# main.net
KiCad netlist of a schematic drawn in EAGLE
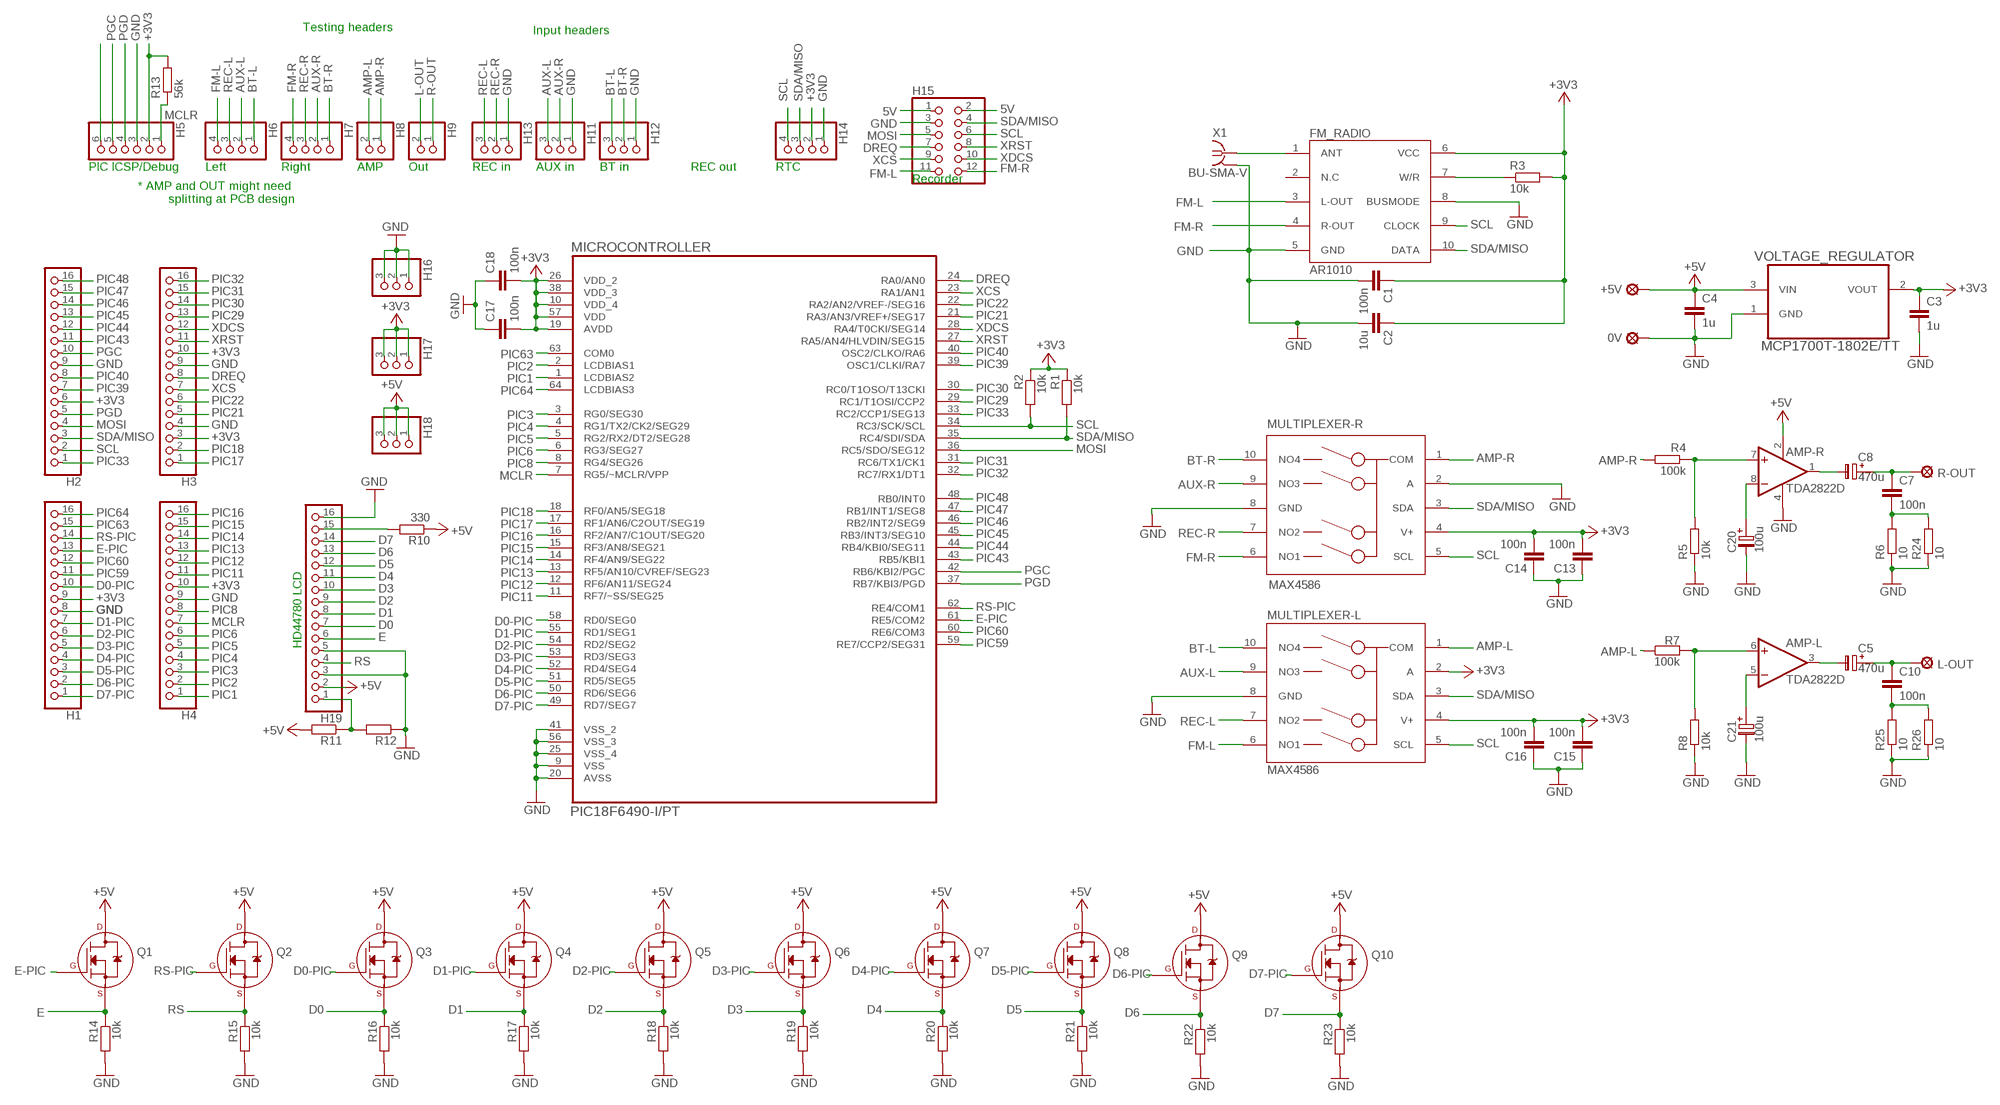
[diagram p0: schematic, sheet 1]

(export (version "E")
  (design (tool "Eeschema 10.0.6"))
  (components
    (comp (ref "+5V")
      (value "LSP11")
      (footprint "eagle-import:LSP11")
      (libsource (lib "eagle-import") (part "LSP11"))
    )
    (comp (ref "0V")
      (value "LSP11")
      (footprint "eagle-import:LSP11")
      (libsource (lib "eagle-import") (part "LSP11"))
    )
    (comp (ref "AMP-")
      (value "TDA2822D")
      (footprint "eagle-import:SO08")
      (libsource (lib "eagle-import") (part "TDA2822D"))
    )
    (comp (ref "C1")
      (value "100n")
      (footprint "eagle-import:C0805")
      (libsource (lib "eagle-import") (part "C-EUC0805"))
    )
    (comp (ref "C2")
      (value "10u")
      (footprint "eagle-import:C0805")
      (libsource (lib "eagle-import") (part "C-EUC0805"))
    )
    (comp (ref "C3")
      (value "1u")
      (footprint "eagle-import:C0805")
      (libsource (lib "eagle-import") (part "C-EUC0805"))
    )
    (comp (ref "C4")
      (value "1u")
      (footprint "eagle-import:C0805")
      (libsource (lib "eagle-import") (part "C-EUC0805"))
    )
    (comp (ref "C5")
      (value "470u")
      (footprint "eagle-import:SV-G")
      (libsource (lib "eagle-import") (part "C-PR-SMD-SV-G"))
    )
    (comp (ref "C7")
      (value "100n")
      (footprint "eagle-import:C0805")
      (libsource (lib "eagle-import") (part "C-EUC0805"))
    )
    (comp (ref "C8")
      (value "470u")
      (footprint "eagle-import:SV-G")
      (libsource (lib "eagle-import") (part "C-PR-SMD-SV-G"))
    )
    (comp (ref "C10")
      (value "100n")
      (footprint "eagle-import:C0805")
      (libsource (lib "eagle-import") (part "C-EUC0805"))
    )
    (comp (ref "C13")
      (value "100n")
      (footprint "eagle-import:C0805")
      (libsource (lib "eagle-import") (part "C-EUC0805"))
    )
    (comp (ref "C14")
      (value "100n")
      (footprint "eagle-import:C0805")
      (libsource (lib "eagle-import") (part "C-EUC0805"))
    )
    (comp (ref "C15")
      (value "100n")
      (footprint "eagle-import:C0805")
      (libsource (lib "eagle-import") (part "C-EUC0805"))
    )
    (comp (ref "C16")
      (value "100n")
      (footprint "eagle-import:C0805")
      (libsource (lib "eagle-import") (part "C-EUC0805"))
    )
    (comp (ref "C17")
      (value "100n")
      (footprint "eagle-import:C0805")
      (libsource (lib "eagle-import") (part "C-EUC0805"))
    )
    (comp (ref "C18")
      (value "100n")
      (footprint "eagle-import:C0805")
      (libsource (lib "eagle-import") (part "C-EUC0805"))
    )
    (comp (ref "C20")
      (value "100u")
      (footprint "eagle-import:SV-D")
      (libsource (lib "eagle-import") (part "C-PR-SMD-SV-D"))
    )
    (comp (ref "C21")
      (value "100u")
      (footprint "eagle-import:SV-D")
      (libsource (lib "eagle-import") (part "C-PR-SMD-SV-D"))
    )
    (comp (ref "H1")
      (value "PINHD-1X16")
      (footprint "eagle-import:1X16")
      (libsource (lib "eagle-import") (part "PINHD-1X16"))
    )
    (comp (ref "H2")
      (value "PINHD-1X16")
      (footprint "eagle-import:1X16")
      (libsource (lib "eagle-import") (part "PINHD-1X16"))
    )
    (comp (ref "H3")
      (value "PINHD-1X16")
      (footprint "eagle-import:1X16")
      (libsource (lib "eagle-import") (part "PINHD-1X16"))
    )
    (comp (ref "H4")
      (value "PINHD-1X16")
      (footprint "eagle-import:1X16")
      (libsource (lib "eagle-import") (part "PINHD-1X16"))
    )
    (comp (ref "H5")
      (value "PINHD-1X6")
      (footprint "eagle-import:1X06")
      (libsource (lib "eagle-import") (part "PINHD-1X6"))
    )
    (comp (ref "H6")
      (value "PINHD-1X4")
      (footprint "eagle-import:1X04")
      (libsource (lib "eagle-import") (part "PINHD-1X4"))
    )
    (comp (ref "H7")
      (value "PINHD-1X4")
      (footprint "eagle-import:1X04")
      (libsource (lib "eagle-import") (part "PINHD-1X4"))
    )
    (comp (ref "H8")
      (value "PINHD-1X2")
      (footprint "eagle-import:1X02")
      (libsource (lib "eagle-import") (part "PINHD-1X2"))
    )
    (comp (ref "H9")
      (value "PINHD-1X2")
      (footprint "eagle-import:1X02")
      (libsource (lib "eagle-import") (part "PINHD-1X2"))
    )
    (comp (ref "H11")
      (value "PINHD-1X3")
      (footprint "eagle-import:1X03")
      (libsource (lib "eagle-import") (part "PINHD-1X3"))
    )
    (comp (ref "H12")
      (value "PINHD-1X3")
      (footprint "eagle-import:1X03")
      (libsource (lib "eagle-import") (part "PINHD-1X3"))
    )
    (comp (ref "H13")
      (value "PINHD-1X3")
      (footprint "eagle-import:1X03")
      (libsource (lib "eagle-import") (part "PINHD-1X3"))
    )
    (comp (ref "H14")
      (value "PINHD-1X4/90")
      (footprint "eagle-import:1X04_90")
      (libsource (lib "eagle-import") (part "PINHD-1X4/90"))
    )
    (comp (ref "H15")
      (value "PINHD-2X6")
      (footprint "eagle-import:2X06")
      (libsource (lib "eagle-import") (part "PINHD-2X6"))
    )
    (comp (ref "H16")
      (value "PINHD-1X3")
      (footprint "eagle-import:1X03")
      (libsource (lib "eagle-import") (part "PINHD-1X3"))
    )
    (comp (ref "H17")
      (value "PINHD-1X3")
      (footprint "eagle-import:1X03")
      (libsource (lib "eagle-import") (part "PINHD-1X3"))
    )
    (comp (ref "H18")
      (value "PINHD-1X3")
      (footprint "eagle-import:1X03")
      (libsource (lib "eagle-import") (part "PINHD-1X3"))
    )
    (comp (ref "H19")
      (value "PINHD-1X16")
      (footprint "eagle-import:1X16")
      (libsource (lib "eagle-import") (part "PINHD-1X16"))
    )
    (comp (ref "L-OUT")
      (value "LSP10")
      (footprint "eagle-import:LSP10")
      (libsource (lib "eagle-import") (part "LSP10"))
    )
    (comp (ref "MICROCONTROLLER")
      (value "PIC18F6490-I/PT")
      (footprint "eagle-import:QFP50P1200X1200X120-64N")
      (libsource (lib "eagle-import") (part "PIC18F6490-I/PT"))
    )
    (comp (ref "Q1")
      (value "2N7000_SOT23")
      (footprint "eagle-import:SOT-23")
      (libsource (lib "eagle-import") (part "2N700_SOT230"))
    )
    (comp (ref "Q2")
      (value "2N7000_SOT23")
      (footprint "eagle-import:SOT-23")
      (libsource (lib "eagle-import") (part "2N700_SOT230"))
    )
    (comp (ref "Q3")
      (value "2N7000_SOT23")
      (footprint "eagle-import:SOT-23")
      (libsource (lib "eagle-import") (part "2N700_SOT230"))
    )
    (comp (ref "Q4")
      (value "2N7000_SOT23")
      (footprint "eagle-import:SOT-23")
      (libsource (lib "eagle-import") (part "2N700_SOT230"))
    )
    (comp (ref "Q5")
      (value "2N7000_SOT23")
      (footprint "eagle-import:SOT-23")
      (libsource (lib "eagle-import") (part "2N700_SOT230"))
    )
    (comp (ref "Q6")
      (value "2N7000_SOT23")
      (footprint "eagle-import:SOT-23")
      (libsource (lib "eagle-import") (part "2N700_SOT230"))
    )
    (comp (ref "Q7")
      (value "2N7000_SOT23")
      (footprint "eagle-import:SOT-23")
      (libsource (lib "eagle-import") (part "2N700_SOT230"))
    )
    (comp (ref "Q8")
      (value "2N7000_SOT23")
      (footprint "eagle-import:SOT-23")
      (libsource (lib "eagle-import") (part "2N700_SOT230"))
    )
    (comp (ref "Q9")
      (value "2N7000_SOT23")
      (footprint "eagle-import:SOT-23")
      (libsource (lib "eagle-import") (part "2N700_SOT230"))
    )
    (comp (ref "Q10")
      (value "2N7000_SOT23")
      (footprint "eagle-import:SOT-23")
      (libsource (lib "eagle-import") (part "2N700_SOT230"))
    )
    (comp (ref "R-OUT")
      (value "LSP10")
      (footprint "eagle-import:LSP10")
      (libsource (lib "eagle-import") (part "LSP10"))
    )
    (comp (ref "R1")
      (value "10k")
      (footprint "eagle-import:M0805")
      (libsource (lib "eagle-import") (part "R-EU_M0805"))
    )
    (comp (ref "R2")
      (value "10k")
      (footprint "eagle-import:M0805")
      (libsource (lib "eagle-import") (part "R-EU_M0805"))
    )
    (comp (ref "R3")
      (value "10k")
      (footprint "eagle-import:M0805")
      (libsource (lib "eagle-import") (part "R-EU_M0805"))
    )
    (comp (ref "R4")
      (value "100k")
      (footprint "eagle-import:M0805")
      (libsource (lib "eagle-import") (part "R-EU_M0805"))
    )
    (comp (ref "R5")
      (value "10k")
      (footprint "eagle-import:M0805")
      (libsource (lib "eagle-import") (part "R-EU_M0805"))
    )
    (comp (ref "R6")
      (value "10")
      (footprint "eagle-import:M0805")
      (libsource (lib "eagle-import") (part "R-EU_M0805"))
    )
    (comp (ref "R7")
      (value "100k")
      (footprint "eagle-import:M0805")
      (libsource (lib "eagle-import") (part "R-EU_M0805"))
    )
    (comp (ref "R8")
      (value "10k")
      (footprint "eagle-import:M0805")
      (libsource (lib "eagle-import") (part "R-EU_M0805"))
    )
    (comp (ref "R10")
      (value "330")
      (footprint "eagle-import:M0805")
      (libsource (lib "eagle-import") (part "R-EU_M0805"))
    )
    (comp (ref "R11")
      (value "R-EU_M0805")
      (footprint "eagle-import:M0805")
      (libsource (lib "eagle-import") (part "R-EU_M0805"))
    )
    (comp (ref "R12")
      (value "R-EU_M0805")
      (footprint "eagle-import:M0805")
      (libsource (lib "eagle-import") (part "R-EU_M0805"))
    )
    (comp (ref "R13")
      (value "56k")
      (footprint "eagle-import:M0805")
      (libsource (lib "eagle-import") (part "R-EU_M0805"))
    )
    (comp (ref "R14")
      (value "10k")
      (footprint "eagle-import:M0805")
      (libsource (lib "eagle-import") (part "R-EU_M0805"))
    )
    (comp (ref "R15")
      (value "10k")
      (footprint "eagle-import:M0805")
      (libsource (lib "eagle-import") (part "R-EU_M0805"))
    )
    (comp (ref "R16")
      (value "10k")
      (footprint "eagle-import:M0805")
      (libsource (lib "eagle-import") (part "R-EU_M0805"))
    )
    (comp (ref "R17")
      (value "10k")
      (footprint "eagle-import:M0805")
      (libsource (lib "eagle-import") (part "R-EU_M0805"))
    )
    (comp (ref "R18")
      (value "10k")
      (footprint "eagle-import:M0805")
      (libsource (lib "eagle-import") (part "R-EU_M0805"))
    )
    (comp (ref "R19")
      (value "10k")
      (footprint "eagle-import:M0805")
      (libsource (lib "eagle-import") (part "R-EU_M0805"))
    )
    (comp (ref "R20")
      (value "10k")
      (footprint "eagle-import:M0805")
      (libsource (lib "eagle-import") (part "R-EU_M0805"))
    )
    (comp (ref "R21")
      (value "10k")
      (footprint "eagle-import:M0805")
      (libsource (lib "eagle-import") (part "R-EU_M0805"))
    )
    (comp (ref "R22")
      (value "10k")
      (footprint "eagle-import:M0805")
      (libsource (lib "eagle-import") (part "R-EU_M0805"))
    )
    (comp (ref "R23")
      (value "10k")
      (footprint "eagle-import:M0805")
      (libsource (lib "eagle-import") (part "R-EU_M0805"))
    )
    (comp (ref "R24")
      (value "10")
      (footprint "eagle-import:M0805")
      (libsource (lib "eagle-import") (part "R-EU_M0805"))
    )
    (comp (ref "R25")
      (value "10")
      (footprint "eagle-import:M0805")
      (libsource (lib "eagle-import") (part "R-EU_M0805"))
    )
    (comp (ref "R26")
      (value "10")
      (footprint "eagle-import:M0805")
      (libsource (lib "eagle-import") (part "R-EU_M0805"))
    )
    (comp (ref "U$1")
      (value "MAX4586")
      (footprint "eagle-import:UMAX10")
      (fields (field (name "VAL") "MAX4586"))
      (libsource (lib "eagle-import") (part "MAX4586"))
    )
    (comp (ref "U$2")
      (value "AR1010")
      (footprint "eagle-import:AR1010")
      (fields (field (name "VAL") "AR1010"))
      (libsource (lib "eagle-import") (part "AR1010"))
    )
    (comp (ref "U$3")
      (value "MAX4586")
      (footprint "eagle-import:UMAX10")
      (fields (field (name "VAL") "MAX4586"))
      (libsource (lib "eagle-import") (part "MAX4586"))
    )
    (comp (ref "VOLTAGE_REGULATOR")
      (value "MCP1700T-1802E/TT")
      (footprint "eagle-import:SOT95P237X112-3N")
      (libsource (lib "eagle-import") (part "MCP1700T-1802E/TT"))
    )
    (comp (ref "X1")
      (value "BU-SMA-V")
      (footprint "eagle-import:BU-SMA-V")
      (libsource (lib "eagle-import") (part "BU-SMA-V"))
    )
  )
  (nets
    (net (code "1") (name "+3V3") (class "Default")
      (node (ref "C1") (pin "1") (pinfunction "1_1") (pintype "passive"))
      (node (ref "C13") (pin "2") (pinfunction "2_2") (pintype "passive"))
      (node (ref "C14") (pin "2") (pinfunction "2_2") (pintype "passive"))
      (node (ref "C15") (pin "2") (pinfunction "2_2") (pintype "passive"))
      (node (ref "C16") (pin "2") (pinfunction "2_2") (pintype "passive"))
      (node (ref "C17") (pin "2") (pinfunction "2_2") (pintype "passive"))
      (node (ref "C18") (pin "2") (pinfunction "2_2") (pintype "passive"))
      (node (ref "C2") (pin "1") (pinfunction "1_1") (pintype "passive"))
      (node (ref "C3") (pin "1") (pinfunction "1_1") (pintype "passive"))
      (node (ref "H1") (pin "9") (pinfunction "9_9") (pintype "passive"))
      (node (ref "H14") (pin "2") (pinfunction "2_2") (pintype "passive"))
      (node (ref "H17") (pin "1") (pinfunction "1_1") (pintype "passive"))
      (node (ref "H17") (pin "2") (pinfunction "2_2") (pintype "passive"))
      (node (ref "H17") (pin "3") (pinfunction "3_3") (pintype "passive"))
      (node (ref "H2") (pin "6") (pinfunction "6_6") (pintype "passive"))
      (node (ref "H3") (pin "10") (pinfunction "10_10") (pintype "passive"))
      (node (ref "H3") (pin "3") (pinfunction "3_3") (pintype "passive"))
      (node (ref "H4") (pin "10") (pinfunction "10_10") (pintype "passive"))
      (node (ref "H5") (pin "2") (pinfunction "2_2") (pintype "passive"))
      (node (ref "MICROCONTROLLER") (pin "10") (pinfunction "VDD_4_10") (pintype "power_in"))
      (node (ref "MICROCONTROLLER") (pin "19") (pinfunction "AVDD_19") (pintype "power_in"))
      (node (ref "MICROCONTROLLER") (pin "26") (pinfunction "VDD_2_26") (pintype "power_in"))
      (node (ref "MICROCONTROLLER") (pin "38") (pinfunction "VDD_3_38") (pintype "power_in"))
      (node (ref "MICROCONTROLLER") (pin "57") (pinfunction "VDD_57") (pintype "power_in"))
      (node (ref "R1") (pin "1") (pinfunction "1_1") (pintype "passive"))
      (node (ref "R13") (pin "2") (pinfunction "2_2") (pintype "passive"))
      (node (ref "R2") (pin "1") (pinfunction "1_1") (pintype "passive"))
      (node (ref "R3") (pin "2") (pinfunction "2_2") (pintype "passive"))
      (node (ref "U$1") (pin "4") (pinfunction "V+_4") (pintype "bidirectional"))
      (node (ref "U$2") (pin "6") (pinfunction "VCC_6") (pintype "bidirectional"))
      (node (ref "U$3") (pin "2") (pinfunction "A_2") (pintype "bidirectional"))
      (node (ref "U$3") (pin "4") (pinfunction "V+_4") (pintype "bidirectional"))
      (node (ref "VOLTAGE_REGULATOR") (pin "2") (pinfunction "VOUT_2") (pintype "output"))
    )
    (net (code "2") (name "+5V") (class "Default")
      (node (ref "+5V") (pin "MP") (pinfunction "MP_MP") (pintype "passive"))
      (node (ref "AMP-") (pin "2") (pinfunction "V+_2") (pintype "power_in"))
      (node (ref "C4") (pin "1") (pinfunction "1_1") (pintype "passive"))
      (node (ref "H18") (pin "1") (pinfunction "1_1") (pintype "passive"))
      (node (ref "H18") (pin "2") (pinfunction "2_2") (pintype "passive"))
      (node (ref "H18") (pin "3") (pinfunction "3_3") (pintype "passive"))
      (node (ref "H19") (pin "2") (pinfunction "2_2") (pintype "passive"))
      (node (ref "Q1") (pin "3") (pinfunction "D_3") (pintype "bidirectional"))
      (node (ref "Q10") (pin "3") (pinfunction "D_3") (pintype "bidirectional"))
      (node (ref "Q2") (pin "3") (pinfunction "D_3") (pintype "bidirectional"))
      (node (ref "Q3") (pin "3") (pinfunction "D_3") (pintype "bidirectional"))
      (node (ref "Q4") (pin "3") (pinfunction "D_3") (pintype "bidirectional"))
      (node (ref "Q5") (pin "3") (pinfunction "D_3") (pintype "bidirectional"))
      (node (ref "Q6") (pin "3") (pinfunction "D_3") (pintype "bidirectional"))
      (node (ref "Q7") (pin "3") (pinfunction "D_3") (pintype "bidirectional"))
      (node (ref "Q8") (pin "3") (pinfunction "D_3") (pintype "bidirectional"))
      (node (ref "Q9") (pin "3") (pinfunction "D_3") (pintype "bidirectional"))
      (node (ref "R10") (pin "1") (pinfunction "1_1") (pintype "passive"))
      (node (ref "R11") (pin "2") (pinfunction "2_2") (pintype "passive"))
      (node (ref "VOLTAGE_REGULATOR") (pin "3") (pinfunction "VIN_3") (pintype "input"))
    )
    (net (code "3") (name "/5V") (class "Default")
      (node (ref "H15") (pin "1") (pinfunction "1_1") (pintype "passive"))
      (node (ref "H15") (pin "2") (pinfunction "2_2") (pintype "passive"))
    )
    (net (code "4") (name "/AMP-L") (class "Default")
      (node (ref "H8") (pin "2") (pinfunction "2_2") (pintype "passive"))
      (node (ref "R7") (pin "1") (pinfunction "1_1") (pintype "passive"))
      (node (ref "U$3") (pin "1") (pinfunction "COM_1") (pintype "bidirectional"))
    )
    (net (code "5") (name "/AMP-R") (class "Default")
      (node (ref "H8") (pin "1") (pinfunction "1_1") (pintype "passive"))
      (node (ref "R4") (pin "2") (pinfunction "2_2") (pintype "passive"))
      (node (ref "U$1") (pin "1") (pinfunction "COM_1") (pintype "bidirectional"))
    )
    (net (code "6") (name "/AUX-L") (class "Default")
      (node (ref "H11") (pin "3") (pinfunction "3_3") (pintype "passive"))
      (node (ref "H6") (pin "2") (pinfunction "2_2") (pintype "passive"))
      (node (ref "U$3") (pin "9") (pinfunction "NO3_9") (pintype "bidirectional"))
    )
    (net (code "7") (name "/AUX-R") (class "Default")
      (node (ref "H11") (pin "2") (pinfunction "2_2") (pintype "passive"))
      (node (ref "H7") (pin "2") (pinfunction "2_2") (pintype "passive"))
      (node (ref "U$1") (pin "9") (pinfunction "NO3_9") (pintype "bidirectional"))
    )
    (net (code "8") (name "/BT-L") (class "Default")
      (node (ref "H12") (pin "3") (pinfunction "3_3") (pintype "passive"))
      (node (ref "H6") (pin "1") (pinfunction "1_1") (pintype "passive"))
      (node (ref "U$3") (pin "10") (pinfunction "NO4_10") (pintype "bidirectional"))
    )
    (net (code "9") (name "/BT-R") (class "Default")
      (node (ref "H12") (pin "2") (pinfunction "2_2") (pintype "passive"))
      (node (ref "H7") (pin "1") (pinfunction "1_1") (pintype "passive"))
      (node (ref "U$1") (pin "10") (pinfunction "NO4_10") (pintype "bidirectional"))
    )
    (net (code "10") (name "/D0") (class "Default")
      (node (ref "H19") (pin "7") (pinfunction "7_7") (pintype "passive"))
      (node (ref "Q3") (pin "2") (pinfunction "S_2") (pintype "bidirectional"))
      (node (ref "R16") (pin "1") (pinfunction "1_1") (pintype "passive"))
    )
    (net (code "11") (name "/D0-PIC") (class "Default")
      (node (ref "H1") (pin "10") (pinfunction "10_10") (pintype "passive"))
      (node (ref "MICROCONTROLLER") (pin "58") (pinfunction "RD0/SEG0_58") (pintype "bidirectional"))
      (node (ref "Q3") (pin "1") (pinfunction "G_1") (pintype "tri_state"))
    )
    (net (code "12") (name "/D1") (class "Default")
      (node (ref "H19") (pin "8") (pinfunction "8_8") (pintype "passive"))
      (node (ref "Q4") (pin "2") (pinfunction "S_2") (pintype "bidirectional"))
      (node (ref "R17") (pin "1") (pinfunction "1_1") (pintype "passive"))
    )
    (net (code "13") (name "/D1-PIC") (class "Default")
      (node (ref "H1") (pin "7") (pinfunction "7_7") (pintype "passive"))
      (node (ref "MICROCONTROLLER") (pin "55") (pinfunction "RD1/SEG1_55") (pintype "bidirectional"))
      (node (ref "Q4") (pin "1") (pinfunction "G_1") (pintype "tri_state"))
    )
    (net (code "14") (name "/D2") (class "Default")
      (node (ref "H19") (pin "9") (pinfunction "9_9") (pintype "passive"))
      (node (ref "Q5") (pin "2") (pinfunction "S_2") (pintype "bidirectional"))
      (node (ref "R18") (pin "1") (pinfunction "1_1") (pintype "passive"))
    )
    (net (code "15") (name "/D2-PIC") (class "Default")
      (node (ref "H1") (pin "6") (pinfunction "6_6") (pintype "passive"))
      (node (ref "MICROCONTROLLER") (pin "54") (pinfunction "RD2/SEG2_54") (pintype "bidirectional"))
      (node (ref "Q5") (pin "1") (pinfunction "G_1") (pintype "tri_state"))
    )
    (net (code "16") (name "/D3") (class "Default")
      (node (ref "H19") (pin "10") (pinfunction "10_10") (pintype "passive"))
      (node (ref "Q6") (pin "2") (pinfunction "S_2") (pintype "bidirectional"))
      (node (ref "R19") (pin "1") (pinfunction "1_1") (pintype "passive"))
    )
    (net (code "17") (name "/D3-PIC") (class "Default")
      (node (ref "H1") (pin "5") (pinfunction "5_5") (pintype "passive"))
      (node (ref "MICROCONTROLLER") (pin "53") (pinfunction "RD3/SEG3_53") (pintype "bidirectional"))
      (node (ref "Q6") (pin "1") (pinfunction "G_1") (pintype "tri_state"))
    )
    (net (code "18") (name "/D4") (class "Default")
      (node (ref "H19") (pin "11") (pinfunction "11_11") (pintype "passive"))
      (node (ref "Q7") (pin "2") (pinfunction "S_2") (pintype "bidirectional"))
      (node (ref "R20") (pin "1") (pinfunction "1_1") (pintype "passive"))
    )
    (net (code "19") (name "/D4-PIC") (class "Default")
      (node (ref "H1") (pin "4") (pinfunction "4_4") (pintype "passive"))
      (node (ref "MICROCONTROLLER") (pin "52") (pinfunction "RD4/SEG4_52") (pintype "bidirectional"))
      (node (ref "Q7") (pin "1") (pinfunction "G_1") (pintype "tri_state"))
    )
    (net (code "20") (name "/D5") (class "Default")
      (node (ref "H19") (pin "12") (pinfunction "12_12") (pintype "passive"))
      (node (ref "Q8") (pin "2") (pinfunction "S_2") (pintype "bidirectional"))
      (node (ref "R21") (pin "1") (pinfunction "1_1") (pintype "passive"))
    )
    (net (code "21") (name "/D5-PIC") (class "Default")
      (node (ref "H1") (pin "3") (pinfunction "3_3") (pintype "passive"))
      (node (ref "MICROCONTROLLER") (pin "51") (pinfunction "RD5/SEG5_51") (pintype "bidirectional"))
      (node (ref "Q8") (pin "1") (pinfunction "G_1") (pintype "tri_state"))
    )
    (net (code "22") (name "/D6") (class "Default")
      (node (ref "H19") (pin "13") (pinfunction "13_13") (pintype "passive"))
      (node (ref "Q9") (pin "2") (pinfunction "S_2") (pintype "bidirectional"))
      (node (ref "R22") (pin "1") (pinfunction "1_1") (pintype "passive"))
    )
    (net (code "23") (name "/D6-PIC") (class "Default")
      (node (ref "H1") (pin "2") (pinfunction "2_2") (pintype "passive"))
      (node (ref "MICROCONTROLLER") (pin "50") (pinfunction "RD6/SEG6_50") (pintype "bidirectional"))
      (node (ref "Q9") (pin "1") (pinfunction "G_1") (pintype "tri_state"))
    )
    (net (code "24") (name "/D7") (class "Default")
      (node (ref "H19") (pin "14") (pinfunction "14_14") (pintype "passive"))
      (node (ref "Q10") (pin "2") (pinfunction "S_2") (pintype "bidirectional"))
      (node (ref "R23") (pin "1") (pinfunction "1_1") (pintype "passive"))
    )
    (net (code "25") (name "/D7-PIC") (class "Default")
      (node (ref "H1") (pin "1") (pinfunction "1_1") (pintype "passive"))
      (node (ref "MICROCONTROLLER") (pin "49") (pinfunction "RD7/SEG7_49") (pintype "bidirectional"))
      (node (ref "Q10") (pin "1") (pinfunction "G_1") (pintype "tri_state"))
    )
    (net (code "26") (name "/DREQ") (class "Default")
      (node (ref "H15") (pin "7") (pinfunction "7_7") (pintype "passive"))
      (node (ref "H3") (pin "8") (pinfunction "8_8") (pintype "passive"))
      (node (ref "MICROCONTROLLER") (pin "24") (pinfunction "RA0/AN0_24") (pintype "bidirectional"))
    )
    (net (code "27") (name "/E") (class "Default")
      (node (ref "H19") (pin "6") (pinfunction "6_6") (pintype "passive"))
      (node (ref "Q1") (pin "2") (pinfunction "S_2") (pintype "bidirectional"))
      (node (ref "R14") (pin "1") (pinfunction "1_1") (pintype "passive"))
    )
    (net (code "28") (name "/E-PIC") (class "Default")
      (node (ref "H1") (pin "13") (pinfunction "13_13") (pintype "passive"))
      (node (ref "MICROCONTROLLER") (pin "61") (pinfunction "RE5/COM2_61") (pintype "bidirectional"))
      (node (ref "Q1") (pin "1") (pinfunction "G_1") (pintype "tri_state"))
    )
    (net (code "29") (name "/FM-L") (class "Default")
      (node (ref "H15") (pin "11") (pinfunction "11_11") (pintype "passive"))
      (node (ref "H6") (pin "4") (pinfunction "4_4") (pintype "passive"))
      (node (ref "U$2") (pin "3") (pinfunction "L-OUT_3") (pintype "bidirectional"))
      (node (ref "U$3") (pin "6") (pinfunction "NO1_6") (pintype "bidirectional"))
    )
    (net (code "30") (name "/FM-R") (class "Default")
      (node (ref "H15") (pin "12") (pinfunction "12_12") (pintype "passive"))
      (node (ref "H7") (pin "4") (pinfunction "4_4") (pintype "passive"))
      (node (ref "U$1") (pin "6") (pinfunction "NO1_6") (pintype "bidirectional"))
      (node (ref "U$2") (pin "4") (pinfunction "R-OUT_4") (pintype "bidirectional"))
    )
    (net (code "31") (name "/L-OUT") (class "Default")
      (node (ref "C10") (pin "1") (pinfunction "1_1") (pintype "passive"))
      (node (ref "C5") (pin "+") (pinfunction "+_+") (pintype "passive"))
      (node (ref "H9") (pin "2") (pinfunction "2_2") (pintype "passive"))
      (node (ref "L-OUT") (pin "MP") (pinfunction "MP_MP") (pintype "passive"))
    )
    (net (code "32") (name "/MCLR") (class "Default")
      (node (ref "H4") (pin "7") (pinfunction "7_7") (pintype "passive"))
      (node (ref "H5") (pin "1") (pinfunction "1_1") (pintype "passive"))
      (node (ref "MICROCONTROLLER") (pin "7") (pinfunction "RG5/~{MCLR/VPP}_7") (pintype "bidirectional"))
      (node (ref "R13") (pin "1") (pinfunction "1_1") (pintype "passive"))
    )
    (net (code "33") (name "/MOSI") (class "Default")
      (node (ref "H15") (pin "5") (pinfunction "5_5") (pintype "passive"))
      (node (ref "H2") (pin "4") (pinfunction "4_4") (pintype "passive"))
      (node (ref "MICROCONTROLLER") (pin "36") (pinfunction "RC5/SDO/SEG12_36") (pintype "bidirectional"))
    )
    (net (code "34") (name "/PGC") (class "Default")
      (node (ref "H2") (pin "10") (pinfunction "10_10") (pintype "passive"))
      (node (ref "H5") (pin "5") (pinfunction "5_5") (pintype "passive"))
      (node (ref "MICROCONTROLLER") (pin "42") (pinfunction "RB6/KBI2/PGC_42") (pintype "bidirectional"))
    )
    (net (code "35") (name "/PGD") (class "Default")
      (node (ref "H2") (pin "5") (pinfunction "5_5") (pintype "passive"))
      (node (ref "H5") (pin "4") (pinfunction "4_4") (pintype "passive"))
      (node (ref "MICROCONTROLLER") (pin "37") (pinfunction "RB7/KBI3/PGD_37") (pintype "bidirectional"))
    )
    (net (code "36") (name "/PIC1") (class "Default")
      (node (ref "H4") (pin "1") (pinfunction "1_1") (pintype "passive"))
      (node (ref "MICROCONTROLLER") (pin "1") (pinfunction "LCDBIAS2_1") (pintype "input"))
    )
    (net (code "37") (name "/PIC2") (class "Default")
      (node (ref "H4") (pin "2") (pinfunction "2_2") (pintype "passive"))
      (node (ref "MICROCONTROLLER") (pin "2") (pinfunction "LCDBIAS1_2") (pintype "input"))
    )
    (net (code "38") (name "/PIC3") (class "Default")
      (node (ref "H4") (pin "3") (pinfunction "3_3") (pintype "passive"))
      (node (ref "MICROCONTROLLER") (pin "3") (pinfunction "RG0/SEG30_3") (pintype "bidirectional"))
    )
    (net (code "39") (name "/PIC4") (class "Default")
      (node (ref "H4") (pin "4") (pinfunction "4_4") (pintype "passive"))
      (node (ref "MICROCONTROLLER") (pin "4") (pinfunction "RG1/TX2/CK2/SEG29_4") (pintype "bidirectional"))
    )
    (net (code "40") (name "/PIC5") (class "Default")
      (node (ref "H4") (pin "5") (pinfunction "5_5") (pintype "passive"))
      (node (ref "MICROCONTROLLER") (pin "5") (pinfunction "RG2/RX2/DT2/SEG28_5") (pintype "bidirectional"))
    )
    (net (code "41") (name "/PIC6") (class "Default")
      (node (ref "H4") (pin "6") (pinfunction "6_6") (pintype "passive"))
      (node (ref "MICROCONTROLLER") (pin "6") (pinfunction "RG3/SEG27_6") (pintype "bidirectional"))
    )
    (net (code "42") (name "/PIC8") (class "Default")
      (node (ref "H4") (pin "8") (pinfunction "8_8") (pintype "passive"))
      (node (ref "MICROCONTROLLER") (pin "8") (pinfunction "RG4/SEG26_8") (pintype "bidirectional"))
    )
    (net (code "43") (name "/PIC11") (class "Default")
      (node (ref "H4") (pin "11") (pinfunction "11_11") (pintype "passive"))
      (node (ref "MICROCONTROLLER") (pin "11") (pinfunction "RF7/~{SS/SEG25}_11") (pintype "bidirectional"))
    )
    (net (code "44") (name "/PIC12") (class "Default")
      (node (ref "H4") (pin "12") (pinfunction "12_12") (pintype "passive"))
      (node (ref "MICROCONTROLLER") (pin "12") (pinfunction "RF6/AN11/SEG24_12") (pintype "bidirectional"))
    )
    (net (code "45") (name "/PIC13") (class "Default")
      (node (ref "H4") (pin "13") (pinfunction "13_13") (pintype "passive"))
      (node (ref "MICROCONTROLLER") (pin "13") (pinfunction "RF5/AN10/CVREF/SEG23_13") (pintype "bidirectional"))
    )
    (net (code "46") (name "/PIC14") (class "Default")
      (node (ref "H4") (pin "14") (pinfunction "14_14") (pintype "passive"))
      (node (ref "MICROCONTROLLER") (pin "14") (pinfunction "RF4/AN9/SEG22_14") (pintype "bidirectional"))
    )
    (net (code "47") (name "/PIC15") (class "Default")
      (node (ref "H4") (pin "15") (pinfunction "15_15") (pintype "passive"))
      (node (ref "MICROCONTROLLER") (pin "15") (pinfunction "RF3/AN8/SEG21_15") (pintype "bidirectional"))
    )
    (net (code "48") (name "/PIC16") (class "Default")
      (node (ref "H4") (pin "16") (pinfunction "16_16") (pintype "passive"))
      (node (ref "MICROCONTROLLER") (pin "16") (pinfunction "RF2/AN7/C1OUT/SEG20_16") (pintype "bidirectional"))
    )
    (net (code "49") (name "/PIC17") (class "Default")
      (node (ref "H3") (pin "1") (pinfunction "1_1") (pintype "passive"))
      (node (ref "MICROCONTROLLER") (pin "17") (pinfunction "RF1/AN6/C2OUT/SEG19_17") (pintype "bidirectional"))
    )
    (net (code "50") (name "/PIC18") (class "Default")
      (node (ref "H3") (pin "2") (pinfunction "2_2") (pintype "passive"))
      (node (ref "MICROCONTROLLER") (pin "18") (pinfunction "RF0/AN5/SEG18_18") (pintype "bidirectional"))
    )
    (net (code "51") (name "/PIC21") (class "Default")
      (node (ref "H3") (pin "5") (pinfunction "5_5") (pintype "passive"))
      (node (ref "MICROCONTROLLER") (pin "21") (pinfunction "RA3/AN3/VREF+/SEG17_21") (pintype "bidirectional"))
    )
    (net (code "52") (name "/PIC22") (class "Default")
      (node (ref "H3") (pin "6") (pinfunction "6_6") (pintype "passive"))
      (node (ref "MICROCONTROLLER") (pin "22") (pinfunction "RA2/AN2/VREF-/SEG16_22") (pintype "bidirectional"))
    )
    (net (code "53") (name "/PIC29") (class "Default")
      (node (ref "H3") (pin "13") (pinfunction "13_13") (pintype "passive"))
      (node (ref "MICROCONTROLLER") (pin "29") (pinfunction "RC1/T1OSI/CCP2_29") (pintype "bidirectional"))
    )
    (net (code "54") (name "/PIC30") (class "Default")
      (node (ref "H3") (pin "14") (pinfunction "14_14") (pintype "passive"))
      (node (ref "MICROCONTROLLER") (pin "30") (pinfunction "RC0/T1OSO/T13CKI_30") (pintype "bidirectional"))
    )
    (net (code "55") (name "/PIC31") (class "Default")
      (node (ref "H3") (pin "15") (pinfunction "15_15") (pintype "passive"))
      (node (ref "MICROCONTROLLER") (pin "31") (pinfunction "RC6/TX1/CK1_31") (pintype "bidirectional"))
    )
    (net (code "56") (name "/PIC32") (class "Default")
      (node (ref "H3") (pin "16") (pinfunction "16_16") (pintype "passive"))
      (node (ref "MICROCONTROLLER") (pin "32") (pinfunction "RC7/RX1/DT1_32") (pintype "bidirectional"))
    )
    (net (code "57") (name "/PIC33") (class "Default")
      (node (ref "H2") (pin "1") (pinfunction "1_1") (pintype "passive"))
      (node (ref "MICROCONTROLLER") (pin "33") (pinfunction "RC2/CCP1/SEG13_33") (pintype "bidirectional"))
    )
    (net (code "58") (name "/PIC39") (class "Default")
      (node (ref "H2") (pin "7") (pinfunction "7_7") (pintype "passive"))
      (node (ref "MICROCONTROLLER") (pin "39") (pinfunction "OSC1/CLKI/RA7_39") (pintype "bidirectional"))
    )
    (net (code "59") (name "/PIC40") (class "Default")
      (node (ref "H2") (pin "8") (pinfunction "8_8") (pintype "passive"))
      (node (ref "MICROCONTROLLER") (pin "40") (pinfunction "OSC2/CLKO/RA6_40") (pintype "bidirectional"))
    )
    (net (code "60") (name "/PIC43") (class "Default")
      (node (ref "H2") (pin "11") (pinfunction "11_11") (pintype "passive"))
      (node (ref "MICROCONTROLLER") (pin "43") (pinfunction "RB5/KBI1_43") (pintype "bidirectional"))
    )
    (net (code "61") (name "/PIC44") (class "Default")
      (node (ref "H2") (pin "12") (pinfunction "12_12") (pintype "passive"))
      (node (ref "MICROCONTROLLER") (pin "44") (pinfunction "RB4/KBI0/SEG11_44") (pintype "bidirectional"))
    )
    (net (code "62") (name "/PIC45") (class "Default")
      (node (ref "H2") (pin "13") (pinfunction "13_13") (pintype "passive"))
      (node (ref "MICROCONTROLLER") (pin "45") (pinfunction "RB3/INT3/SEG10_45") (pintype "bidirectional"))
    )
    (net (code "63") (name "/PIC46") (class "Default")
      (node (ref "H2") (pin "14") (pinfunction "14_14") (pintype "passive"))
      (node (ref "MICROCONTROLLER") (pin "46") (pinfunction "RB2/INT2/SEG9_46") (pintype "bidirectional"))
    )
    (net (code "64") (name "/PIC47") (class "Default")
      (node (ref "H2") (pin "15") (pinfunction "15_15") (pintype "passive"))
      (node (ref "MICROCONTROLLER") (pin "47") (pinfunction "RB1/INT1/SEG8_47") (pintype "bidirectional"))
    )
    (net (code "65") (name "/PIC48") (class "Default")
      (node (ref "H2") (pin "16") (pinfunction "16_16") (pintype "passive"))
      (node (ref "MICROCONTROLLER") (pin "48") (pinfunction "RB0/INT0_48") (pintype "bidirectional"))
    )
    (net (code "66") (name "/PIC59") (class "Default")
      (node (ref "H1") (pin "11") (pinfunction "11_11") (pintype "passive"))
      (node (ref "MICROCONTROLLER") (pin "59") (pinfunction "RE7/CCP2/SEG31_59") (pintype "bidirectional"))
    )
    (net (code "67") (name "/PIC60") (class "Default")
      (node (ref "H1") (pin "12") (pinfunction "12_12") (pintype "passive"))
      (node (ref "MICROCONTROLLER") (pin "60") (pinfunction "RE6/COM3_60") (pintype "bidirectional"))
    )
    (net (code "68") (name "/PIC63") (class "Default")
      (node (ref "H1") (pin "15") (pinfunction "15_15") (pintype "passive"))
      (node (ref "MICROCONTROLLER") (pin "63") (pinfunction "COM0_63") (pintype "passive"))
    )
    (net (code "69") (name "/PIC64") (class "Default")
      (node (ref "H1") (pin "16") (pinfunction "16_16") (pintype "passive"))
      (node (ref "MICROCONTROLLER") (pin "64") (pinfunction "LCDBIAS3_64") (pintype "input"))
    )
    (net (code "70") (name "/R-OUT") (class "Default")
      (node (ref "C7") (pin "1") (pinfunction "1_1") (pintype "passive"))
      (node (ref "C8") (pin "+") (pinfunction "+_+") (pintype "passive"))
      (node (ref "H9") (pin "1") (pinfunction "1_1") (pintype "passive"))
      (node (ref "R-OUT") (pin "MP") (pinfunction "MP_MP") (pintype "passive"))
    )
    (net (code "71") (name "/REC-L") (class "Default")
      (node (ref "H13") (pin "3") (pinfunction "3_3") (pintype "passive"))
      (node (ref "H6") (pin "3") (pinfunction "3_3") (pintype "passive"))
      (node (ref "U$3") (pin "7") (pinfunction "NO2_7") (pintype "bidirectional"))
    )
    (net (code "72") (name "/REC-R") (class "Default")
      (node (ref "H13") (pin "2") (pinfunction "2_2") (pintype "passive"))
      (node (ref "H7") (pin "3") (pinfunction "3_3") (pintype "passive"))
      (node (ref "U$1") (pin "7") (pinfunction "NO2_7") (pintype "bidirectional"))
    )
    (net (code "73") (name "/RS") (class "Default")
      (node (ref "H19") (pin "4") (pinfunction "4_4") (pintype "passive"))
      (node (ref "Q2") (pin "2") (pinfunction "S_2") (pintype "bidirectional"))
      (node (ref "R15") (pin "1") (pinfunction "1_1") (pintype "passive"))
    )
    (net (code "74") (name "/RS-PIC") (class "Default")
      (node (ref "H1") (pin "14") (pinfunction "14_14") (pintype "passive"))
      (node (ref "MICROCONTROLLER") (pin "62") (pinfunction "RE4/COM1_62") (pintype "bidirectional"))
      (node (ref "Q2") (pin "1") (pinfunction "G_1") (pintype "tri_state"))
    )
    (net (code "75") (name "/SCL") (class "Default")
      (node (ref "H14") (pin "4") (pinfunction "4_4") (pintype "passive"))
      (node (ref "H15") (pin "6") (pinfunction "6_6") (pintype "passive"))
      (node (ref "H2") (pin "2") (pinfunction "2_2") (pintype "passive"))
      (node (ref "MICROCONTROLLER") (pin "34") (pinfunction "RC3/SCK/SCL_34") (pintype "bidirectional"))
      (node (ref "R2") (pin "2") (pinfunction "2_2") (pintype "passive"))
      (node (ref "U$1") (pin "5") (pinfunction "SCL_5") (pintype "bidirectional"))
      (node (ref "U$2") (pin "9") (pinfunction "CLOCK_9") (pintype "bidirectional"))
      (node (ref "U$3") (pin "5") (pinfunction "SCL_5") (pintype "bidirectional"))
    )
    (net (code "76") (name "/SDA{slash}MISO") (class "Default")
      (node (ref "H14") (pin "3") (pinfunction "3_3") (pintype "passive"))
      (node (ref "H15") (pin "4") (pinfunction "4_4") (pintype "passive"))
      (node (ref "H2") (pin "3") (pinfunction "3_3") (pintype "passive"))
      (node (ref "MICROCONTROLLER") (pin "35") (pinfunction "RC4/SDI/SDA_35") (pintype "bidirectional"))
      (node (ref "R1") (pin "2") (pinfunction "2_2") (pintype "passive"))
      (node (ref "U$1") (pin "3") (pinfunction "SDA_3") (pintype "bidirectional"))
      (node (ref "U$2") (pin "10") (pinfunction "DATA_10") (pintype "bidirectional"))
      (node (ref "U$3") (pin "3") (pinfunction "SDA_3") (pintype "bidirectional"))
    )
    (net (code "77") (name "/XCS") (class "Default")
      (node (ref "H15") (pin "9") (pinfunction "9_9") (pintype "passive"))
      (node (ref "H3") (pin "7") (pinfunction "7_7") (pintype "passive"))
      (node (ref "MICROCONTROLLER") (pin "23") (pinfunction "RA1/AN1_23") (pintype "bidirectional"))
    )
    (net (code "78") (name "/XDCS") (class "Default")
      (node (ref "H15") (pin "10") (pinfunction "10_10") (pintype "passive"))
      (node (ref "H3") (pin "12") (pinfunction "12_12") (pintype "passive"))
      (node (ref "MICROCONTROLLER") (pin "28") (pinfunction "RA4/T0CKI/SEG14_28") (pintype "bidirectional"))
    )
    (net (code "79") (name "/XRST") (class "Default")
      (node (ref "H15") (pin "8") (pinfunction "8_8") (pintype "passive"))
      (node (ref "H3") (pin "11") (pinfunction "11_11") (pintype "passive"))
      (node (ref "MICROCONTROLLER") (pin "27") (pinfunction "RA5/AN4/HLVDIN/SEG15_27") (pintype "bidirectional"))
    )
    (net (code "80") (name "GND") (class "Default")
      (node (ref "0V") (pin "MP") (pinfunction "MP_MP") (pintype "passive"))
      (node (ref "AMP-") (pin "4") (pinfunction "V-_4") (pintype "power_in"))
      (node (ref "C1") (pin "2") (pinfunction "2_2") (pintype "passive"))
      (node (ref "C13") (pin "1") (pinfunction "1_1") (pintype "passive"))
      (node (ref "C14") (pin "1") (pinfunction "1_1") (pintype "passive"))
      (node (ref "C15") (pin "1") (pinfunction "1_1") (pintype "passive"))
      (node (ref "C16") (pin "1") (pinfunction "1_1") (pintype "passive"))
      (node (ref "C17") (pin "1") (pinfunction "1_1") (pintype "passive"))
      (node (ref "C18") (pin "1") (pinfunction "1_1") (pintype "passive"))
      (node (ref "C2") (pin "2") (pinfunction "2_2") (pintype "passive"))
      (node (ref "C20") (pin "-") (pinfunction "-_-") (pintype "passive"))
      (node (ref "C21") (pin "-") (pinfunction "-_-") (pintype "passive"))
      (node (ref "C3") (pin "2") (pinfunction "2_2") (pintype "passive"))
      (node (ref "C4") (pin "2") (pinfunction "2_2") (pintype "passive"))
      (node (ref "H1") (pin "8") (pinfunction "8_8") (pintype "passive"))
      (node (ref "H11") (pin "1") (pinfunction "1_1") (pintype "passive"))
      (node (ref "H12") (pin "1") (pinfunction "1_1") (pintype "passive"))
      (node (ref "H13") (pin "1") (pinfunction "1_1") (pintype "passive"))
      (node (ref "H14") (pin "1") (pinfunction "1_1") (pintype "passive"))
      (node (ref "H15") (pin "3") (pinfunction "3_3") (pintype "passive"))
      (node (ref "H16") (pin "1") (pinfunction "1_1") (pintype "passive"))
      (node (ref "H16") (pin "2") (pinfunction "2_2") (pintype "passive"))
      (node (ref "H16") (pin "3") (pinfunction "3_3") (pintype "passive"))
      (node (ref "H19") (pin "16") (pinfunction "16_16") (pintype "passive"))
      (node (ref "H19") (pin "3") (pinfunction "3_3") (pintype "passive"))
      (node (ref "H19") (pin "5") (pinfunction "5_5") (pintype "passive"))
      (node (ref "H2") (pin "9") (pinfunction "9_9") (pintype "passive"))
      (node (ref "H3") (pin "4") (pinfunction "4_4") (pintype "passive"))
      (node (ref "H3") (pin "9") (pinfunction "9_9") (pintype "passive"))
      (node (ref "H4") (pin "9") (pinfunction "9_9") (pintype "passive"))
      (node (ref "H5") (pin "3") (pinfunction "3_3") (pintype "passive"))
      (node (ref "MICROCONTROLLER") (pin "20") (pinfunction "AVSS_20") (pintype "power_in"))
      (node (ref "MICROCONTROLLER") (pin "25") (pinfunction "VSS_4_25") (pintype "power_in"))
      (node (ref "MICROCONTROLLER") (pin "41") (pinfunction "VSS_2_41") (pintype "power_in"))
      (node (ref "MICROCONTROLLER") (pin "56") (pinfunction "VSS_3_56") (pintype "power_in"))
      (node (ref "MICROCONTROLLER") (pin "9") (pinfunction "VSS_9") (pintype "power_in"))
      (node (ref "R12") (pin "1") (pinfunction "1_1") (pintype "passive"))
      (node (ref "R14") (pin "2") (pinfunction "2_2") (pintype "passive"))
      (node (ref "R15") (pin "2") (pinfunction "2_2") (pintype "passive"))
      (node (ref "R16") (pin "2") (pinfunction "2_2") (pintype "passive"))
      (node (ref "R17") (pin "2") (pinfunction "2_2") (pintype "passive"))
      (node (ref "R18") (pin "2") (pinfunction "2_2") (pintype "passive"))
      (node (ref "R19") (pin "2") (pinfunction "2_2") (pintype "passive"))
      (node (ref "R20") (pin "2") (pinfunction "2_2") (pintype "passive"))
      (node (ref "R21") (pin "2") (pinfunction "2_2") (pintype "passive"))
      (node (ref "R22") (pin "2") (pinfunction "2_2") (pintype "passive"))
      (node (ref "R23") (pin "2") (pinfunction "2_2") (pintype "passive"))
      (node (ref "R24") (pin "1") (pinfunction "1_1") (pintype "passive"))
      (node (ref "R25") (pin "1") (pinfunction "1_1") (pintype "passive"))
      (node (ref "R26") (pin "1") (pinfunction "1_1") (pintype "passive"))
      (node (ref "R5") (pin "1") (pinfunction "1_1") (pintype "passive"))
      (node (ref "R6") (pin "1") (pinfunction "1_1") (pintype "passive"))
      (node (ref "R8") (pin "1") (pinfunction "1_1") (pintype "passive"))
      (node (ref "U$1") (pin "2") (pinfunction "A_2") (pintype "bidirectional"))
      (node (ref "U$1") (pin "8") (pinfunction "GND_8") (pintype "bidirectional"))
      (node (ref "U$2") (pin "5") (pinfunction "GND_5") (pintype "bidirectional"))
      (node (ref "U$2") (pin "8") (pinfunction "BUSMODE_8") (pintype "bidirectional"))
      (node (ref "U$3") (pin "8") (pinfunction "GND_8") (pintype "bidirectional"))
      (node (ref "VOLTAGE_REGULATOR") (pin "1") (pinfunction "GND_1") (pintype "passive"))
      (node (ref "X1") (pin "2") (pinfunction "2_2") (pintype "passive"))
      (node (ref "X1") (pin "3") (pinfunction "2_3") (pintype "passive"))
      (node (ref "X1") (pin "4") (pinfunction "2_4") (pintype "passive"))
      (node (ref "X1") (pin "5") (pinfunction "2_5") (pintype "passive"))
    )
    (net (code "81") (name "Net-(AMP-A-+IN)") (class "Default")
      (node (ref "AMP-") (pin "6") (pinfunction "+IN_6") (pintype "input"))
      (node (ref "R7") (pin "2") (pinfunction "2_2") (pintype "passive"))
      (node (ref "R8") (pin "2") (pinfunction "2_2") (pintype "passive"))
    )
    (net (code "82") (name "Net-(AMP-A--IN)") (class "Default")
      (node (ref "AMP-") (pin "5") (pinfunction "-IN_5") (pintype "input"))
      (node (ref "C21") (pin "+") (pinfunction "+_+") (pintype "passive"))
    )
    (net (code "83") (name "Net-(AMP-A-OUT)") (class "Default")
      (node (ref "AMP-") (pin "3") (pinfunction "OUT_3") (pintype "output"))
      (node (ref "C5") (pin "-") (pinfunction "-_-") (pintype "passive"))
    )
    (net (code "84") (name "Net-(AMP-B-+IN)") (class "Default")
      (node (ref "AMP-") (pin "7") (pinfunction "+IN_7") (pintype "input"))
      (node (ref "R4") (pin "1") (pinfunction "1_1") (pintype "passive"))
      (node (ref "R5") (pin "2") (pinfunction "2_2") (pintype "passive"))
    )
    (net (code "85") (name "Net-(AMP-B--IN)") (class "Default")
      (node (ref "AMP-") (pin "8") (pinfunction "-IN_8") (pintype "input"))
      (node (ref "C20") (pin "+") (pinfunction "+_+") (pintype "passive"))
    )
    (net (code "86") (name "Net-(AMP-B-OUT)") (class "Default")
      (node (ref "AMP-") (pin "1") (pinfunction "OUT_1") (pintype "output"))
      (node (ref "C8") (pin "-") (pinfunction "-_-") (pintype "passive"))
    )
    (net (code "87") (name "Net-(C7-Pad2)") (class "Default")
      (node (ref "C7") (pin "2") (pinfunction "2_2") (pintype "passive"))
      (node (ref "R24") (pin "2") (pinfunction "2_2") (pintype "passive"))
      (node (ref "R6") (pin "2") (pinfunction "2_2") (pintype "passive"))
    )
    (net (code "88") (name "Net-(C10-Pad2)") (class "Default")
      (node (ref "C10") (pin "2") (pinfunction "2_2") (pintype "passive"))
      (node (ref "R25") (pin "2") (pinfunction "2_2") (pintype "passive"))
      (node (ref "R26") (pin "2") (pinfunction "2_2") (pintype "passive"))
    )
    (net (code "89") (name "Net-(H19-Pad1)") (class "Default")
      (node (ref "H19") (pin "1") (pinfunction "1_1") (pintype "passive"))
      (node (ref "R11") (pin "1") (pinfunction "1_1") (pintype "passive"))
      (node (ref "R12") (pin "2") (pinfunction "2_2") (pintype "passive"))
    )
    (net (code "90") (name "Net-(H19-Pad15)") (class "Default")
      (node (ref "H19") (pin "15") (pinfunction "15_15") (pintype "passive"))
      (node (ref "R10") (pin "2") (pinfunction "2_2") (pintype "passive"))
    )
    (net (code "91") (name "Net-(U$2-ANT)") (class "Default")
      (node (ref "U$2") (pin "1") (pinfunction "ANT_1") (pintype "bidirectional"))
      (node (ref "X1") (pin "1") (pinfunction "1_1") (pintype "passive"))
    )
    (net (code "92") (name "Net-(U$2-W{slash}R)") (class "Default")
      (node (ref "R3") (pin "1") (pinfunction "1_1") (pintype "passive"))
      (node (ref "U$2") (pin "7") (pinfunction "W/R_7") (pintype "bidirectional"))
    )
    (net (code "93") (name "unconnected-(H5-Pad6)") (class "Default")
      (node (ref "H5") (pin "6") (pinfunction "6_6") (pintype "passive"))
    )
    (net (code "94") (name "unconnected-(U$2-N.C-Pad2)") (class "Default")
      (node (ref "U$2") (pin "2") (pinfunction "N.C_2") (pintype "bidirectional"))
    )
  )
)
